# Schem1.net
KiCad netlist of a schematic drawn in EAGLE
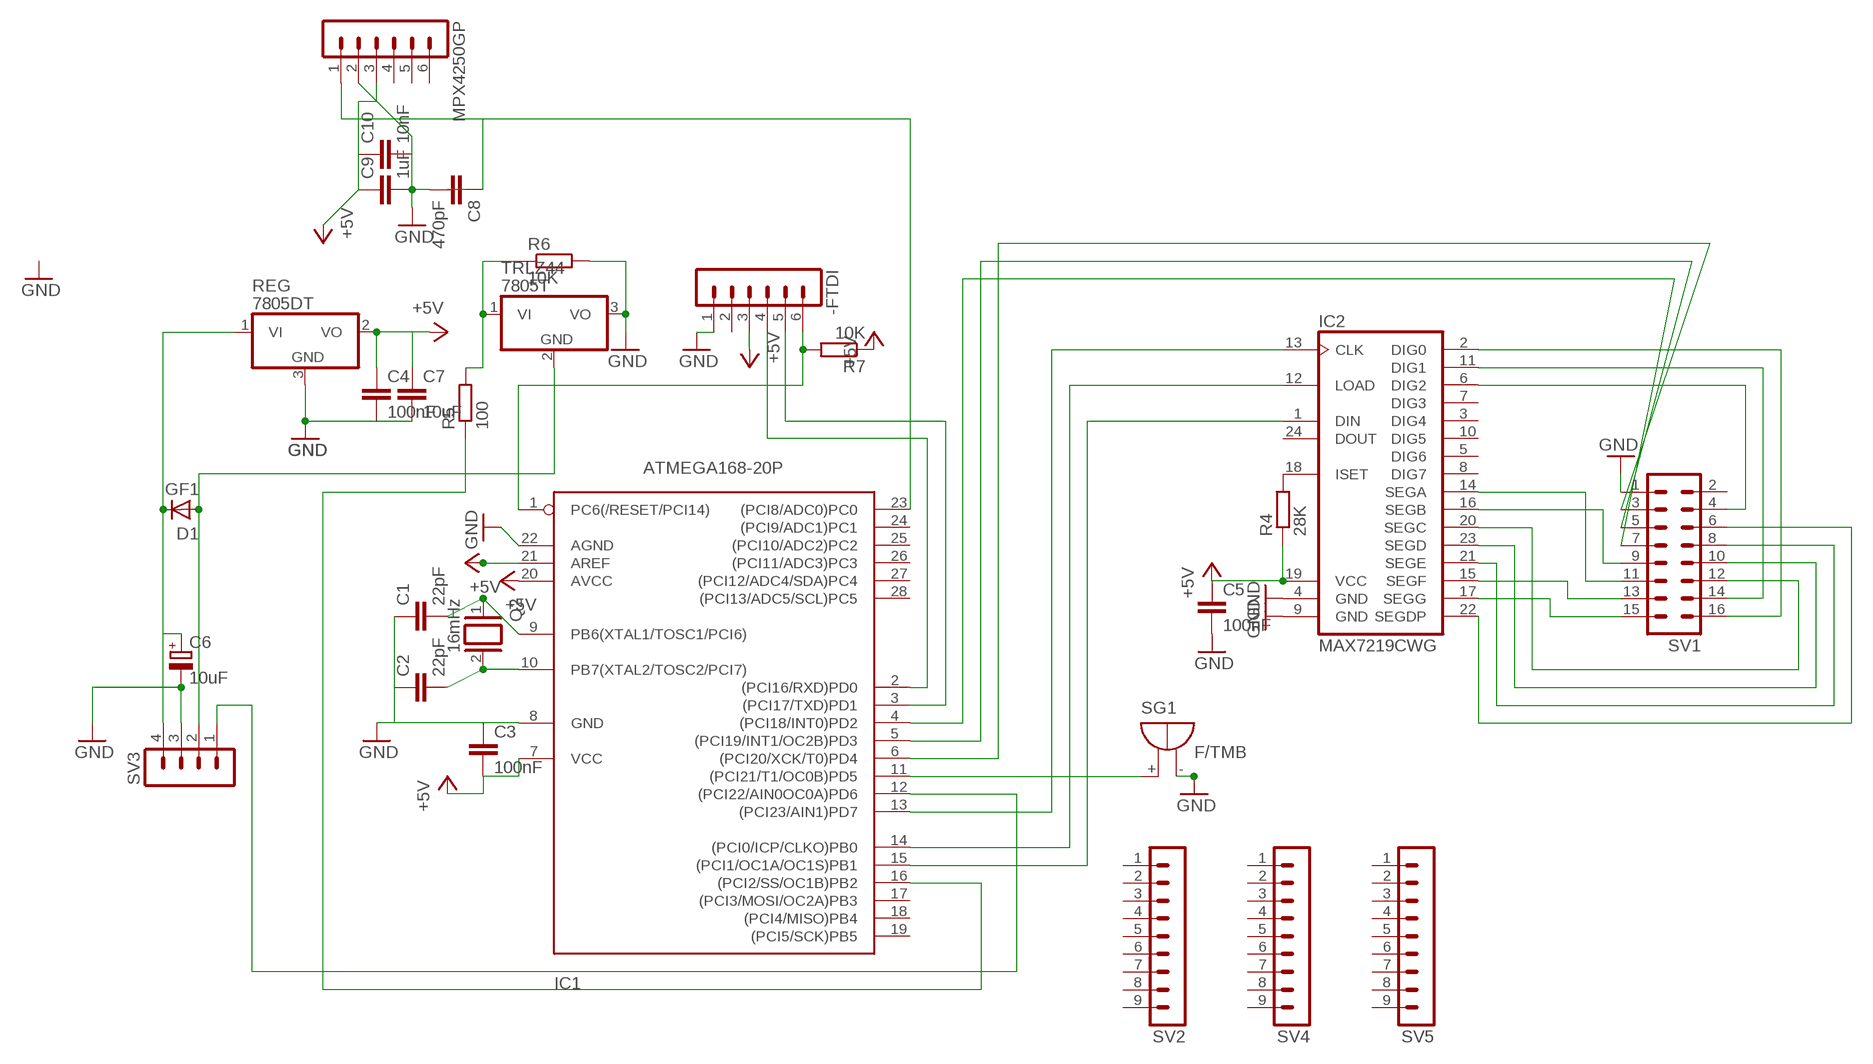
[diagram p0: schematic, sheet 1]

(export (version "E")
  (design (tool "Eeschema 10.0.6"))
  (components
    (comp (ref "-FTDI")
      (value "MA06-1")
      (footprint "eagle-import:MA06-1")
      (libsource (lib "eagle-import") (part "MA06-1"))
    )
    (comp (ref "C1")
      (value "22pF")
      (footprint "eagle-import:C0805")
      (fields (field (name "MF") "MURATA") (field (name "MPN") "ERB21B5C2D220JDX1L"))
      (libsource (lib "eagle-import") (part "C-EUC0805"))
    )
    (comp (ref "C2")
      (value "22pF")
      (footprint "eagle-import:C0805")
      (fields (field (name "MF") "MURATA") (field (name "MPN") "ERB21B5C2D220JDX1L"))
      (libsource (lib "eagle-import") (part "C-EUC0805"))
    )
    (comp (ref "C3")
      (value "100nF")
      (footprint "eagle-import:C0805")
      (fields (field (name "MF") "KEMET") (field (name "MPN") "C0805X104K5RACTU"))
      (libsource (lib "eagle-import") (part "C-EUC0805"))
    )
    (comp (ref "C4")
      (value "100nF")
      (footprint "eagle-import:C0805")
      (fields (field (name "MF") "KEMET") (field (name "MPN") "C0805X104K5RACTU"))
      (libsource (lib "eagle-import") (part "C-EUC0805"))
    )
    (comp (ref "C5")
      (value "100nF")
      (footprint "eagle-import:C0805")
      (fields (field (name "MF") "KEMET") (field (name "MPN") "C0805X104K5RACTU"))
      (libsource (lib "eagle-import") (part "C-EUC0805"))
    )
    (comp (ref "C6")
      (value "10uF")
      (footprint "eagle-import:E2,5-6E")
      (libsource (lib "eagle-import") (part "CPOL-EUE2,5-6E"))
    )
    (comp (ref "C7")
      (value "10uF")
      (footprint "eagle-import:C0805")
      (fields (field (name "MF") "KEMET") (field (name "MPN") "C0805X104K5RACTU"))
      (libsource (lib "eagle-import") (part "C-EUC0805"))
    )
    (comp (ref "C8")
      (value "470pF")
      (footprint "eagle-import:C0805")
      (fields (field (name "MF") "KEMET") (field (name "MPN") "C0805X104K5RACTU"))
      (libsource (lib "eagle-import") (part "C-EUC0805"))
    )
    (comp (ref "C9")
      (value "1uF")
      (footprint "eagle-import:C0805")
      (fields (field (name "MF") "KEMET") (field (name "MPN") "C0805X104K5RACTU"))
      (libsource (lib "eagle-import") (part "C-EUC0805"))
    )
    (comp (ref "C10")
      (value "10nF")
      (footprint "eagle-import:C0805")
      (fields (field (name "MF") "KEMET") (field (name "MPN") "C0805X104K5RACTU"))
      (libsource (lib "eagle-import") (part "C-EUC0805"))
    )
    (comp (ref "D1")
      (value "GF1")
      (footprint "eagle-import:SMA-DO214AC")
      (libsource (lib "eagle-import") (part "GF1"))
    )
    (comp (ref "IC1")
      (value "ATMEGA168-20P")
      (footprint "eagle-import:DIL28-3")
      (libsource (lib "eagle-import") (part "ATMEGA168P-20"))
    )
    (comp (ref "IC2")
      (value "MAX7219CWG")
      (footprint "eagle-import:MAX7219CWG")
      (libsource (lib "eagle-import") (part "MAX7219CWG"))
    )
    (comp (ref "MPX4250GP")
      (value "MA06-1")
      (footprint "eagle-import:MA06-1")
      (libsource (lib "eagle-import") (part "MA06-1"))
    )
    (comp (ref "Q2")
      (value "16mHz")
      (footprint "eagle-import:QS")
      (fields (field (name "MF") "EUROQUARTZ") (field (name "MPN") "16.000MHZ HC49/4H/30/50/40/18PF/ATF"))
      (libsource (lib "eagle-import") (part "XTAL/S"))
    )
    (comp (ref "R4")
      (value "28K")
      (footprint "eagle-import:R0805")
      (libsource (lib "eagle-import") (part "R-EU_R0805"))
    )
    (comp (ref "R5")
      (value "100")
      (footprint "eagle-import:R0805")
      (libsource (lib "eagle-import") (part "R-EU_R0805"))
    )
    (comp (ref "R6")
      (value "10K")
      (footprint "eagle-import:R0805")
      (libsource (lib "eagle-import") (part "R-EU_R0805"))
    )
    (comp (ref "R7")
      (value "10K")
      (footprint "eagle-import:R0805")
      (libsource (lib "eagle-import") (part "R-EU_R0805"))
    )
    (comp (ref "REG")
      (value "7805DT")
      (footprint "eagle-import:TO252")
      (libsource (lib "eagle-import") (part "78DT05"))
    )
    (comp (ref "SG1")
      (value "F/TMB")
      (footprint "eagle-import:F_TMB")
      (libsource (lib "eagle-import") (part "F/TMB"))
    )
    (comp (ref "SV1")
      (value "MA08-2")
      (footprint "eagle-import:MA08-2")
      (libsource (lib "eagle-import") (part "MA08-2"))
    )
    (comp (ref "SV2")
      (value "MA09-1")
      (footprint "eagle-import:MA09-1")
      (libsource (lib "eagle-import") (part "MA09-1"))
    )
    (comp (ref "SV3")
      (value "MA04-1")
      (footprint "eagle-import:MA04-1")
      (libsource (lib "eagle-import") (part "MA04-1"))
    )
    (comp (ref "SV4")
      (value "MA09-1")
      (footprint "eagle-import:MA09-1")
      (libsource (lib "eagle-import") (part "MA09-1"))
    )
    (comp (ref "SV5")
      (value "MA09-1")
      (footprint "eagle-import:MA09-1")
      (libsource (lib "eagle-import") (part "MA09-1"))
    )
    (comp (ref "TRLZ44")
      (value "7805T")
      (footprint "eagle-import:TO220H")
      (libsource (lib "eagle-import") (part "78T05"))
    )
  )
  (nets
    (net (code "1") (name "+5V") (class "Default")
      (node (ref "-FTDI") (pin "3") (pinfunction "3_3") (pintype "passive"))
      (node (ref "C10") (pin "1") (pinfunction "1_1") (pintype "passive"))
      (node (ref "C3") (pin "2") (pinfunction "2_2") (pintype "passive"))
      (node (ref "C4") (pin "1") (pinfunction "1_1") (pintype "passive"))
      (node (ref "C5") (pin "1") (pinfunction "1_1") (pintype "passive"))
      (node (ref "C7") (pin "1") (pinfunction "1_1") (pintype "passive"))
      (node (ref "C9") (pin "1") (pinfunction "1_1") (pintype "passive"))
      (node (ref "IC1") (pin "20") (pinfunction "AVCC_20") (pintype "bidirectional"))
      (node (ref "IC1") (pin "21") (pinfunction "AREF_21") (pintype "bidirectional"))
      (node (ref "IC1") (pin "7") (pinfunction "VCC_7") (pintype "bidirectional"))
      (node (ref "IC2") (pin "19") (pinfunction "VCC_19") (pintype "power_in"))
      (node (ref "MPX4250GP") (pin "3") (pinfunction "3_3") (pintype "passive"))
      (node (ref "R4") (pin "1") (pinfunction "1_1") (pintype "passive"))
      (node (ref "R7") (pin "1") (pinfunction "1_1") (pintype "passive"))
      (node (ref "REG") (pin "2") (pinfunction "VO_2") (pintype "passive"))
    )
    (net (code "2") (name "GND") (class "Default")
      (node (ref "-FTDI") (pin "1") (pinfunction "1_1") (pintype "passive"))
      (node (ref "C1") (pin "1") (pinfunction "1_1") (pintype "passive"))
      (node (ref "C10") (pin "2") (pinfunction "2_2") (pintype "passive"))
      (node (ref "C2") (pin "1") (pinfunction "1_1") (pintype "passive"))
      (node (ref "C3") (pin "1") (pinfunction "1_1") (pintype "passive"))
      (node (ref "C4") (pin "2") (pinfunction "2_2") (pintype "passive"))
      (node (ref "C5") (pin "2") (pinfunction "2_2") (pintype "passive"))
      (node (ref "C6") (pin "-") (pinfunction "-_-") (pintype "passive"))
      (node (ref "C7") (pin "2") (pinfunction "2_2") (pintype "passive"))
      (node (ref "C8") (pin "2") (pinfunction "2_2") (pintype "passive"))
      (node (ref "C9") (pin "2") (pinfunction "2_2") (pintype "passive"))
      (node (ref "IC1") (pin "22") (pinfunction "AGND_22") (pintype "bidirectional"))
      (node (ref "IC1") (pin "8") (pinfunction "GND_8") (pintype "bidirectional"))
      (node (ref "IC2") (pin "4") (pinfunction "GND_4") (pintype "power_in"))
      (node (ref "IC2") (pin "9") (pinfunction "GND_9") (pintype "power_in"))
      (node (ref "MPX4250GP") (pin "2") (pinfunction "2_2") (pintype "passive"))
      (node (ref "R6") (pin "2") (pinfunction "2_2") (pintype "passive"))
      (node (ref "REG") (pin "3") (pinfunction "GND_3") (pintype "passive"))
      (node (ref "SG1") (pin "-") (pinfunction "-_-") (pintype "passive"))
      (node (ref "SV1") (pin "1") (pinfunction "1_1") (pintype "passive"))
      (node (ref "SV3") (pin "3") (pinfunction "3_3") (pintype "passive"))
      (node (ref "TRLZ44") (pin "3") (pinfunction "VO_3") (pintype "passive"))
    )
    (net (code "3") (name "Net-(D1-C)") (class "Default")
      (node (ref "C6") (pin "+") (pinfunction "+_+") (pintype "passive"))
      (node (ref "D1") (pin "K") (pinfunction "C_K") (pintype "passive"))
      (node (ref "REG") (pin "1") (pinfunction "VI_1") (pintype "input"))
      (node (ref "SV3") (pin "4") (pinfunction "4_4") (pintype "passive"))
    )
    (net (code "4") (name "Net-(IC1-(PCI0{slash}ICP{slash}CLKO)PB0)") (class "Default")
      (node (ref "IC1") (pin "14") (pinfunction "(PCI0/ICP/CLKO)PB0_14") (pintype "bidirectional"))
      (node (ref "IC2") (pin "12") (pinfunction "LOAD_12") (pintype "input"))
    )
    (net (code "5") (name "Net-(IC1-(PCI1{slash}OC1A{slash}OC1S)PB1)") (class "Default")
      (node (ref "IC1") (pin "15") (pinfunction "(PCI1/OC1A/OC1S)PB1_15") (pintype "bidirectional"))
      (node (ref "IC2") (pin "1") (pinfunction "DIN_1") (pintype "input"))
    )
    (net (code "6") (name "Net-(IC1-(PCI2{slash}SS{slash}OC1B)PB2)") (class "Default")
      (node (ref "IC1") (pin "16") (pinfunction "(PCI2/SS/OC1B)PB2_16") (pintype "bidirectional"))
      (node (ref "R5") (pin "1") (pinfunction "1_1") (pintype "passive"))
    )
    (net (code "7") (name "Net-(IC1-(PCI8{slash}ADC0)PC0)") (class "Default")
      (node (ref "C8") (pin "1") (pinfunction "1_1") (pintype "passive"))
      (node (ref "IC1") (pin "23") (pinfunction "(PCI8/ADC0)PC0_23") (pintype "bidirectional"))
      (node (ref "MPX4250GP") (pin "1") (pinfunction "1_1") (pintype "passive"))
    )
    (net (code "8") (name "Net-(IC1-(PCI16{slash}RXD)PD0)") (class "Default")
      (node (ref "-FTDI") (pin "4") (pinfunction "4_4") (pintype "passive"))
      (node (ref "IC1") (pin "2") (pinfunction "(PCI16/RXD)PD0_2") (pintype "bidirectional"))
    )
    (net (code "9") (name "Net-(IC1-(PCI17{slash}TXD)PD1)") (class "Default")
      (node (ref "-FTDI") (pin "5") (pinfunction "5_5") (pintype "passive"))
      (node (ref "IC1") (pin "3") (pinfunction "(PCI17/TXD)PD1_3") (pintype "bidirectional"))
    )
    (net (code "10") (name "Net-(IC1-(PCI18{slash}INT0)PD2)") (class "Default")
      (node (ref "IC1") (pin "4") (pinfunction "(PCI18/INT0)PD2_4") (pintype "bidirectional"))
      (node (ref "SV1") (pin "7") (pinfunction "7_7") (pintype "passive"))
    )
    (net (code "11") (name "Net-(IC1-(PCI19{slash}INT1{slash}OC2B)PD3)") (class "Default")
      (node (ref "IC1") (pin "5") (pinfunction "(PCI19/INT1/OC2B)PD3_5") (pintype "bidirectional"))
      (node (ref "SV1") (pin "5") (pinfunction "5_5") (pintype "passive"))
    )
    (net (code "12") (name "Net-(IC1-(PCI20{slash}XCK{slash}T0)PD4)") (class "Default")
      (node (ref "IC1") (pin "6") (pinfunction "(PCI20/XCK/T0)PD4_6") (pintype "bidirectional"))
      (node (ref "SV1") (pin "3") (pinfunction "3_3") (pintype "passive"))
    )
    (net (code "13") (name "Net-(IC1-(PCI21{slash}T1{slash}OC0B)PD5)") (class "Default")
      (node (ref "IC1") (pin "11") (pinfunction "(PCI21/T1/OC0B)PD5_11") (pintype "bidirectional"))
      (node (ref "SG1") (pin "+") (pinfunction "+_+") (pintype "passive"))
    )
    (net (code "14") (name "Net-(IC1-(PCI22{slash}AIN0OC0A)PD6)") (class "Default")
      (node (ref "IC1") (pin "12") (pinfunction "(PCI22/AIN0OC0A)PD6_12") (pintype "bidirectional"))
      (node (ref "SV3") (pin "1") (pinfunction "1_1") (pintype "passive"))
    )
    (net (code "15") (name "Net-(IC1-(PCI23{slash}AIN1)PD7)") (class "Default")
      (node (ref "IC1") (pin "13") (pinfunction "(PCI23/AIN1)PD7_13") (pintype "bidirectional"))
      (node (ref "IC2") (pin "13") (pinfunction "CLK_13") (pintype "input"))
    )
    (net (code "16") (name "Net-(IC1-PB6(XTAL1{slash}TOSC1{slash}PCI6))") (class "Default")
      (node (ref "C1") (pin "2") (pinfunction "2_2") (pintype "passive"))
      (node (ref "IC1") (pin "9") (pinfunction "PB6(XTAL1/TOSC1/PCI6)_9") (pintype "bidirectional"))
      (node (ref "Q2") (pin "1") (pinfunction "1_1") (pintype "passive"))
    )
    (net (code "17") (name "Net-(IC1-PB7(XTAL2{slash}TOSC2{slash}PCI7))") (class "Default")
      (node (ref "C2") (pin "2") (pinfunction "2_2") (pintype "passive"))
      (node (ref "IC1") (pin "10") (pinfunction "PB7(XTAL2/TOSC2/PCI7)_10") (pintype "bidirectional"))
      (node (ref "Q2") (pin "2") (pinfunction "2_2") (pintype "passive"))
    )
    (net (code "18") (name "Net-(IC1-PC6({slash}RESET{slash}PCI14))") (class "Default")
      (node (ref "-FTDI") (pin "6") (pinfunction "6_6") (pintype "passive"))
      (node (ref "IC1") (pin "1") (pinfunction "PC6(/RESET/PCI14)_1") (pintype "bidirectional"))
      (node (ref "R7") (pin "2") (pinfunction "2_2") (pintype "passive"))
    )
    (net (code "19") (name "Net-(IC2-DIG0)") (class "Default")
      (node (ref "IC2") (pin "2") (pinfunction "DIG0_2") (pintype "output"))
      (node (ref "SV1") (pin "16") (pinfunction "16_16") (pintype "passive"))
    )
    (net (code "20") (name "Net-(IC2-DIG1)") (class "Default")
      (node (ref "IC2") (pin "11") (pinfunction "DIG1_11") (pintype "output"))
      (node (ref "SV1") (pin "14") (pinfunction "14_14") (pintype "passive"))
    )
    (net (code "21") (name "Net-(IC2-DIG2)") (class "Default")
      (node (ref "IC2") (pin "6") (pinfunction "DIG2_6") (pintype "output"))
      (node (ref "SV1") (pin "4") (pinfunction "4_4") (pintype "passive"))
    )
    (net (code "22") (name "Net-(IC2-ISET)") (class "Default")
      (node (ref "IC2") (pin "18") (pinfunction "ISET_18") (pintype "input"))
      (node (ref "R4") (pin "2") (pinfunction "2_2") (pintype "passive"))
    )
    (net (code "23") (name "Net-(IC2-SEGA)") (class "Default")
      (node (ref "IC2") (pin "14") (pinfunction "SEGA_14") (pintype "output"))
      (node (ref "SV1") (pin "11") (pinfunction "11_11") (pintype "passive"))
    )
    (net (code "24") (name "Net-(IC2-SEGB)") (class "Default")
      (node (ref "IC2") (pin "16") (pinfunction "SEGB_16") (pintype "output"))
      (node (ref "SV1") (pin "9") (pinfunction "9_9") (pintype "passive"))
    )
    (net (code "25") (name "Net-(IC2-SEGC)") (class "Default")
      (node (ref "IC2") (pin "20") (pinfunction "SEGC_20") (pintype "output"))
      (node (ref "SV1") (pin "12") (pinfunction "12_12") (pintype "passive"))
    )
    (net (code "26") (name "Net-(IC2-SEGD)") (class "Default")
      (node (ref "IC2") (pin "23") (pinfunction "SEGD_23") (pintype "output"))
      (node (ref "SV1") (pin "10") (pinfunction "10_10") (pintype "passive"))
    )
    (net (code "27") (name "Net-(IC2-SEGDP)") (class "Default")
      (node (ref "IC2") (pin "22") (pinfunction "SEGDP_22") (pintype "output"))
      (node (ref "SV1") (pin "6") (pinfunction "6_6") (pintype "passive"))
    )
    (net (code "28") (name "Net-(IC2-SEGE)") (class "Default")
      (node (ref "IC2") (pin "21") (pinfunction "SEGE_21") (pintype "output"))
      (node (ref "SV1") (pin "8") (pinfunction "8_8") (pintype "passive"))
    )
    (net (code "29") (name "Net-(IC2-SEGF)") (class "Default")
      (node (ref "IC2") (pin "15") (pinfunction "SEGF_15") (pintype "output"))
      (node (ref "SV1") (pin "13") (pinfunction "13_13") (pintype "passive"))
    )
    (net (code "30") (name "Net-(IC2-SEGG)") (class "Default")
      (node (ref "IC2") (pin "17") (pinfunction "SEGG_17") (pintype "output"))
      (node (ref "SV1") (pin "15") (pinfunction "15_15") (pintype "passive"))
    )
    (net (code "31") (name "Net-(TRLZ44-GND)") (class "Default")
      (node (ref "D1") (pin "A") (pinfunction "A_A") (pintype "passive"))
      (node (ref "SV3") (pin "2") (pinfunction "2_2") (pintype "passive"))
      (node (ref "TRLZ44") (pin "2") (pinfunction "GND_2") (pintype "passive"))
    )
    (net (code "32") (name "Net-(TRLZ44-VI)") (class "Default")
      (node (ref "R5") (pin "2") (pinfunction "2_2") (pintype "passive"))
      (node (ref "R6") (pin "1") (pinfunction "1_1") (pintype "passive"))
      (node (ref "TRLZ44") (pin "1") (pinfunction "VI_1") (pintype "input"))
    )
    (net (code "33") (name "unconnected-(-FTDI-Pad2)") (class "Default")
      (node (ref "-FTDI") (pin "2") (pinfunction "2_2") (pintype "passive"))
    )
    (net (code "34") (name "unconnected-(IC1-(PCI3{slash}MOSI{slash}OC2A)PB3-Pad17)") (class "Default")
      (node (ref "IC1") (pin "17") (pinfunction "(PCI3/MOSI/OC2A)PB3_17") (pintype "bidirectional"))
    )
    (net (code "35") (name "unconnected-(IC1-(PCI4{slash}MISO)PB4-Pad18)") (class "Default")
      (node (ref "IC1") (pin "18") (pinfunction "(PCI4/MISO)PB4_18") (pintype "bidirectional"))
    )
    (net (code "36") (name "unconnected-(IC1-(PCI5{slash}SCK)PB5-Pad19)") (class "Default")
      (node (ref "IC1") (pin "19") (pinfunction "(PCI5/SCK)PB5_19") (pintype "bidirectional"))
    )
    (net (code "37") (name "unconnected-(IC1-(PCI9{slash}ADC1)PC1-Pad24)") (class "Default")
      (node (ref "IC1") (pin "24") (pinfunction "(PCI9/ADC1)PC1_24") (pintype "bidirectional"))
    )
    (net (code "38") (name "unconnected-(IC1-(PCI10{slash}ADC2)PC2-Pad25)") (class "Default")
      (node (ref "IC1") (pin "25") (pinfunction "(PCI10/ADC2)PC2_25") (pintype "bidirectional"))
    )
    (net (code "39") (name "unconnected-(IC1-(PCI11{slash}ADC3)PC3-Pad26)") (class "Default")
      (node (ref "IC1") (pin "26") (pinfunction "(PCI11/ADC3)PC3_26") (pintype "bidirectional"))
    )
    (net (code "40") (name "unconnected-(IC1-(PCI12{slash}ADC4{slash}SDA)PC4-Pad27)") (class "Default")
      (node (ref "IC1") (pin "27") (pinfunction "(PCI12/ADC4/SDA)PC4_27") (pintype "bidirectional"))
    )
    (net (code "41") (name "unconnected-(IC1-(PCI13{slash}ADC5{slash}SCL)PC5-Pad28)") (class "Default")
      (node (ref "IC1") (pin "28") (pinfunction "(PCI13/ADC5/SCL)PC5_28") (pintype "bidirectional"))
    )
    (net (code "42") (name "unconnected-(IC2-DIG3-Pad7)") (class "Default")
      (node (ref "IC2") (pin "7") (pinfunction "DIG3_7") (pintype "output"))
    )
    (net (code "43") (name "unconnected-(IC2-DIG4-Pad3)") (class "Default")
      (node (ref "IC2") (pin "3") (pinfunction "DIG4_3") (pintype "output"))
    )
    (net (code "44") (name "unconnected-(IC2-DIG5-Pad10)") (class "Default")
      (node (ref "IC2") (pin "10") (pinfunction "DIG5_10") (pintype "output"))
    )
    (net (code "45") (name "unconnected-(IC2-DIG6-Pad5)") (class "Default")
      (node (ref "IC2") (pin "5") (pinfunction "DIG6_5") (pintype "output"))
    )
    (net (code "46") (name "unconnected-(IC2-DIG7-Pad8)") (class "Default")
      (node (ref "IC2") (pin "8") (pinfunction "DIG7_8") (pintype "output"))
    )
    (net (code "47") (name "unconnected-(IC2-DOUT-Pad24)") (class "Default")
      (node (ref "IC2") (pin "24") (pinfunction "DOUT_24") (pintype "output"))
    )
    (net (code "48") (name "unconnected-(MPX4250GP-Pad4)") (class "Default")
      (node (ref "MPX4250GP") (pin "4") (pinfunction "4_4") (pintype "passive"))
    )
    (net (code "49") (name "unconnected-(MPX4250GP-Pad5)") (class "Default")
      (node (ref "MPX4250GP") (pin "5") (pinfunction "5_5") (pintype "passive"))
    )
    (net (code "50") (name "unconnected-(MPX4250GP-Pad6)") (class "Default")
      (node (ref "MPX4250GP") (pin "6") (pinfunction "6_6") (pintype "passive"))
    )
    (net (code "51") (name "unconnected-(SV1-Pad2)") (class "Default")
      (node (ref "SV1") (pin "2") (pinfunction "2_2") (pintype "passive"))
    )
    (net (code "52") (name "unconnected-(SV2-Pad1)") (class "Default")
      (node (ref "SV2") (pin "1") (pinfunction "1_1") (pintype "passive"))
    )
    (net (code "53") (name "unconnected-(SV2-Pad2)") (class "Default")
      (node (ref "SV2") (pin "2") (pinfunction "2_2") (pintype "passive"))
    )
    (net (code "54") (name "unconnected-(SV2-Pad3)") (class "Default")
      (node (ref "SV2") (pin "3") (pinfunction "3_3") (pintype "passive"))
    )
    (net (code "55") (name "unconnected-(SV2-Pad4)") (class "Default")
      (node (ref "SV2") (pin "4") (pinfunction "4_4") (pintype "passive"))
    )
    (net (code "56") (name "unconnected-(SV2-Pad5)") (class "Default")
      (node (ref "SV2") (pin "5") (pinfunction "5_5") (pintype "passive"))
    )
    (net (code "57") (name "unconnected-(SV2-Pad6)") (class "Default")
      (node (ref "SV2") (pin "6") (pinfunction "6_6") (pintype "passive"))
    )
    (net (code "58") (name "unconnected-(SV2-Pad7)") (class "Default")
      (node (ref "SV2") (pin "7") (pinfunction "7_7") (pintype "passive"))
    )
    (net (code "59") (name "unconnected-(SV2-Pad8)") (class "Default")
      (node (ref "SV2") (pin "8") (pinfunction "8_8") (pintype "passive"))
    )
    (net (code "60") (name "unconnected-(SV2-Pad9)") (class "Default")
      (node (ref "SV2") (pin "9") (pinfunction "9_9") (pintype "passive"))
    )
    (net (code "61") (name "unconnected-(SV4-Pad1)") (class "Default")
      (node (ref "SV4") (pin "1") (pinfunction "1_1") (pintype "passive"))
    )
    (net (code "62") (name "unconnected-(SV4-Pad2)") (class "Default")
      (node (ref "SV4") (pin "2") (pinfunction "2_2") (pintype "passive"))
    )
    (net (code "63") (name "unconnected-(SV4-Pad3)") (class "Default")
      (node (ref "SV4") (pin "3") (pinfunction "3_3") (pintype "passive"))
    )
    (net (code "64") (name "unconnected-(SV4-Pad4)") (class "Default")
      (node (ref "SV4") (pin "4") (pinfunction "4_4") (pintype "passive"))
    )
    (net (code "65") (name "unconnected-(SV4-Pad5)") (class "Default")
      (node (ref "SV4") (pin "5") (pinfunction "5_5") (pintype "passive"))
    )
    (net (code "66") (name "unconnected-(SV4-Pad6)") (class "Default")
      (node (ref "SV4") (pin "6") (pinfunction "6_6") (pintype "passive"))
    )
    (net (code "67") (name "unconnected-(SV4-Pad7)") (class "Default")
      (node (ref "SV4") (pin "7") (pinfunction "7_7") (pintype "passive"))
    )
    (net (code "68") (name "unconnected-(SV4-Pad8)") (class "Default")
      (node (ref "SV4") (pin "8") (pinfunction "8_8") (pintype "passive"))
    )
    (net (code "69") (name "unconnected-(SV4-Pad9)") (class "Default")
      (node (ref "SV4") (pin "9") (pinfunction "9_9") (pintype "passive"))
    )
    (net (code "70") (name "unconnected-(SV5-Pad1)") (class "Default")
      (node (ref "SV5") (pin "1") (pinfunction "1_1") (pintype "passive"))
    )
    (net (code "71") (name "unconnected-(SV5-Pad2)") (class "Default")
      (node (ref "SV5") (pin "2") (pinfunction "2_2") (pintype "passive"))
    )
    (net (code "72") (name "unconnected-(SV5-Pad3)") (class "Default")
      (node (ref "SV5") (pin "3") (pinfunction "3_3") (pintype "passive"))
    )
    (net (code "73") (name "unconnected-(SV5-Pad4)") (class "Default")
      (node (ref "SV5") (pin "4") (pinfunction "4_4") (pintype "passive"))
    )
    (net (code "74") (name "unconnected-(SV5-Pad5)") (class "Default")
      (node (ref "SV5") (pin "5") (pinfunction "5_5") (pintype "passive"))
    )
    (net (code "75") (name "unconnected-(SV5-Pad6)") (class "Default")
      (node (ref "SV5") (pin "6") (pinfunction "6_6") (pintype "passive"))
    )
    (net (code "76") (name "unconnected-(SV5-Pad7)") (class "Default")
      (node (ref "SV5") (pin "7") (pinfunction "7_7") (pintype "passive"))
    )
    (net (code "77") (name "unconnected-(SV5-Pad8)") (class "Default")
      (node (ref "SV5") (pin "8") (pinfunction "8_8") (pintype "passive"))
    )
    (net (code "78") (name "unconnected-(SV5-Pad9)") (class "Default")
      (node (ref "SV5") (pin "9") (pinfunction "9_9") (pintype "passive"))
    )
  )
)
